# Sheet1.net
KiCad netlist of a schematic drawn in Altium Designer
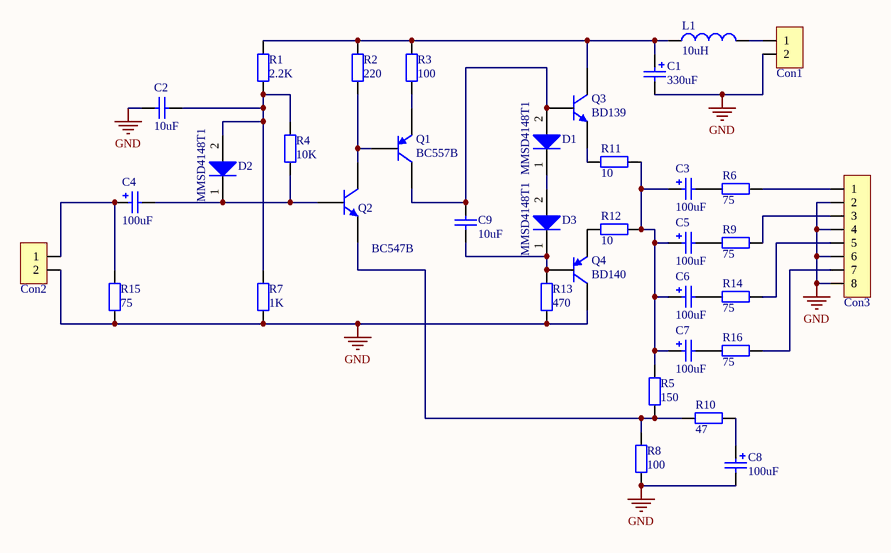
[diagram p0: Sheet1.SchDoc]

(export (version "E")
  (design (tool "Eeschema 10.0.6"))
  (components
    (comp (ref "C1")
      (value "330uF")
      (footprint "CAP Elect 8X4")
      (description "Polarized Capacitor (Radial)")
      (fields (field (name "Comment") "Cap Pol1"))
      (libsource (lib "miscellaneous") (part "Cap Pol1"))
    )
    (comp (ref "C2")
      (value "10uF")
      (footprint "H0805")
      (description "Capacitor")
      (fields (field (name "Comment") "Cap"))
      (libsource (lib "miscellaneous") (part "Cap"))
    )
    (comp (ref "C3")
      (value "100uF")
      (footprint "CAP Elect 5X2.5")
      (description "Polarized Capacitor (Radial)")
      (fields (field (name "Comment") "Cap Pol1"))
      (libsource (lib "miscellaneous") (part "Cap Pol1"))
    )
    (comp (ref "C4")
      (value "100uF")
      (footprint "CAP Elect 5X2.5")
      (description "Polarized Capacitor (Radial)")
      (fields (field (name "Comment") "Cap Pol1"))
      (libsource (lib "miscellaneous") (part "Cap Pol1"))
    )
    (comp (ref "C5")
      (value "100uF")
      (footprint "CAP Elect 5X2.5")
      (description "Polarized Capacitor (Radial)")
      (fields (field (name "Comment") "Cap Pol1"))
      (libsource (lib "miscellaneous") (part "Cap Pol1"))
    )
    (comp (ref "C6")
      (value "100uF")
      (footprint "CAP Elect 5X2.5")
      (description "Polarized Capacitor (Radial)")
      (fields (field (name "Comment") "Cap Pol1"))
      (libsource (lib "miscellaneous") (part "Cap Pol1"))
    )
    (comp (ref "C7")
      (value "100uF")
      (footprint "CAP Elect 5X2.5")
      (description "Polarized Capacitor (Radial)")
      (fields (field (name "Comment") "Cap Pol1"))
      (libsource (lib "miscellaneous") (part "Cap Pol1"))
    )
    (comp (ref "C8")
      (value "100uF")
      (footprint "CAP Elect 5X2.5")
      (description "Polarized Capacitor (Radial)")
      (fields (field (name "Comment") "Cap Pol1"))
      (libsource (lib "miscellaneous") (part "Cap Pol1"))
    )
    (comp (ref "C9")
      (value "10uF")
      (footprint "H0805")
      (description "Capacitor")
      (fields (field (name "Comment") "Cap"))
      (libsource (lib "miscellaneous") (part "Cap"))
    )
    (comp (ref "Con1")
      (value "XH-2A")
      (footprint "XH-2A")
      (description "2.5mm")
      (libsource (lib "Connector") (part "XH-2A"))
    )
    (comp (ref "Con2")
      (value "XH-2A")
      (footprint "XH-2A")
      (description "2.5mm")
      (libsource (lib "") (part "XH-2A_1"))
    )
    (comp (ref "Con3")
      (value "XH-8A")
      (footprint "XH-8A")
      (description "2.5mm")
      (libsource (lib "Connector") (part "XH-8A"))
    )
    (comp (ref "D1")
      (value "MMSD4148T1")
      (footprint "ONSC-SOD-123-2-425-04_V")
      (description "Switching Diode, 2-Pin SOD-123, Tape and Reel")
      (fields (field (name "MANUFACTURER") "On Semiconductor"))
      (libsource (lib "ON Semi Small Signal Switching Diodes") (part "MMSD4148T1"))
    )
    (comp (ref "D2")
      (value "MMSD4148T1")
      (footprint "ONSC-SOD-123-2-425-04_V")
      (description "Switching Diode, 2-Pin SOD-123, Tape and Reel")
      (fields (field (name "MANUFACTURER") "On Semiconductor"))
      (libsource (lib "ON Semi Small Signal Switching Diodes") (part "MMSD4148T1"))
    )
    (comp (ref "D3")
      (value "MMSD4148T1")
      (footprint "ONSC-SOD-123-2-425-04_V")
      (description "Switching Diode, 2-Pin SOD-123, Tape and Reel")
      (fields (field (name "MANUFACTURER") "On Semiconductor"))
      (libsource (lib "ON Semi Small Signal Switching Diodes") (part "MMSD4148T1"))
    )
    (comp (ref "L1")
      (value "10uH")
      (footprint "INDP7870X53N")
      (description "Inductor")
      (fields (field (name "PUBLISHER") "Altium Limited"))
      (libsource (lib "miscellaneous") (part "Inductor"))
    )
    (comp (ref "Q1")
      (value "BC557B")
      (footprint "SOT54")
      (description "PNP General-purpose Transistor")
      (fields (field (name "PUBLISHER") "Altium Limited"))
      (libsource (lib "Philips Discrete BJT - Low Power") (part "BC557B"))
    )
    (comp (ref "Q2")
      (value "BC547B")
      (footprint "SOT54")
      (description "NPN General-purpose Transistor")
      (fields (field (name "PUBLISHER") "Altium Limited"))
      (libsource (lib "Philips Discrete BJT - Low Power") (part "BC547B"))
    )
    (comp (ref "Q3")
      (value "BD139")
      (footprint "TO-126")
      (description "NPN SILICON TRANSISTORS")
      (libsource (lib "miscellaneous") (part "BD139"))
    )
    (comp (ref "Q4")
      (value "BD140")
      (footprint "TO-126")
      (description "PNP SILICON TRANSISTORS")
      (libsource (lib "miscellaneous") (part "BD140"))
    )
    (comp (ref "R1")
      (value "2.2K")
      (footprint "H0805")
      (description "Resistor")
      (fields (field (name "Comment") "Res2") (field (name "PUBLISHER") "Altium Limited"))
      (libsource (lib "") (part "Res2_1"))
    )
    (comp (ref "R2")
      (value "220")
      (footprint "H0805")
      (description "Resistor")
      (fields (field (name "Comment") "Res2") (field (name "PUBLISHER") "Altium Limited"))
      (libsource (lib "") (part "Res2_1"))
    )
    (comp (ref "R3")
      (value "100")
      (footprint "H0805")
      (description "Resistor")
      (fields (field (name "Comment") "Res2") (field (name "PUBLISHER") "Altium Limited"))
      (libsource (lib "") (part "Res2_1"))
    )
    (comp (ref "R4")
      (value "10K")
      (footprint "H0805")
      (description "Resistor")
      (fields (field (name "Comment") "Res2") (field (name "PUBLISHER") "Altium Limited"))
      (libsource (lib "") (part "Res2_1"))
    )
    (comp (ref "R5")
      (value "150")
      (footprint "H0805")
      (description "Resistor")
      (fields (field (name "Comment") "Res2") (field (name "PUBLISHER") "Altium Limited"))
      (libsource (lib "") (part "Res2_1"))
    )
    (comp (ref "R6")
      (value "75")
      (footprint "H0805")
      (description "Resistor")
      (fields (field (name "Comment") "Res2") (field (name "PUBLISHER") "Altium Limited"))
      (libsource (lib "Miscellaneous Devices") (part "Res2"))
    )
    (comp (ref "R7")
      (value "1K")
      (footprint "H0805")
      (description "Resistor")
      (fields (field (name "Comment") "Res2") (field (name "PUBLISHER") "Altium Limited"))
      (libsource (lib "") (part "Res2_1"))
    )
    (comp (ref "R8")
      (value "100")
      (footprint "H0805")
      (description "Resistor")
      (fields (field (name "Comment") "Res2") (field (name "PUBLISHER") "Altium Limited"))
      (libsource (lib "") (part "Res2_1"))
    )
    (comp (ref "R9")
      (value "75")
      (footprint "H0805")
      (description "Resistor")
      (fields (field (name "Comment") "Res2") (field (name "PUBLISHER") "Altium Limited"))
      (libsource (lib "Miscellaneous Devices") (part "Res2"))
    )
    (comp (ref "R10")
      (value "47")
      (footprint "H0805")
      (description "Resistor")
      (fields (field (name "Comment") "Res2") (field (name "PUBLISHER") "Altium Limited"))
      (libsource (lib "Miscellaneous Devices") (part "Res2"))
    )
    (comp (ref "R11")
      (value "10")
      (footprint "H1206")
      (description "Resistor")
      (fields (field (name "Comment") "Res2") (field (name "PUBLISHER") "Altium Limited"))
      (libsource (lib "Miscellaneous Devices") (part "Res2"))
    )
    (comp (ref "R12")
      (value "10")
      (footprint "H1206")
      (description "Resistor")
      (fields (field (name "Comment") "Res2") (field (name "PUBLISHER") "Altium Limited"))
      (libsource (lib "Miscellaneous Devices") (part "Res2"))
    )
    (comp (ref "R13")
      (value "470")
      (footprint "H0805")
      (description "Resistor")
      (fields (field (name "Comment") "Res2") (field (name "PUBLISHER") "Altium Limited"))
      (libsource (lib "") (part "Res2_1"))
    )
    (comp (ref "R14")
      (value "75")
      (footprint "H0805")
      (description "Resistor")
      (fields (field (name "Comment") "Res2") (field (name "PUBLISHER") "Altium Limited"))
      (libsource (lib "Miscellaneous Devices") (part "Res2"))
    )
    (comp (ref "R15")
      (value "75")
      (footprint "H0805")
      (description "Resistor")
      (fields (field (name "Comment") "Res2") (field (name "PUBLISHER") "Altium Limited"))
      (libsource (lib "") (part "Res2_1"))
    )
    (comp (ref "R16")
      (value "75")
      (footprint "H0805")
      (description "Resistor")
      (fields (field (name "Comment") "Res2") (field (name "PUBLISHER") "Altium Limited"))
      (libsource (lib "Miscellaneous Devices") (part "Res2"))
    )
  )
  (nets
    (net (code "1") (name "GND") (class "Default")
      (node (ref "C1") (pin "2") (pinfunction "2_2") (pintype "passive"))
      (node (ref "C2") (pin "2") (pinfunction "2_2") (pintype "passive"))
      (node (ref "C8") (pin "2") (pinfunction "2_2") (pintype "passive"))
      (node (ref "Con1") (pin "2") (pinfunction "2_2") (pintype "passive"))
      (node (ref "Con2") (pin "2") (pinfunction "2_2") (pintype "passive"))
      (node (ref "Con3") (pin "2") (pinfunction "2_2") (pintype "passive"))
      (node (ref "Con3") (pin "4") (pinfunction "4_4") (pintype "passive"))
      (node (ref "Con3") (pin "6") (pinfunction "6_6") (pintype "passive"))
      (node (ref "Con3") (pin "8") (pinfunction "8_8") (pintype "passive"))
      (node (ref "Q4") (pin "2") (pinfunction "C_2") (pintype "passive"))
      (node (ref "R13") (pin "1") (pinfunction "1_1") (pintype "passive"))
      (node (ref "R15") (pin "1") (pinfunction "1_1") (pintype "passive"))
      (node (ref "R7") (pin "1") (pinfunction "1_1") (pintype "passive"))
      (node (ref "R8") (pin "1") (pinfunction "1_1") (pintype "passive"))
    )
    (net (code "2") (name "Net-(C3-Pad1)") (class "Default")
      (node (ref "C3") (pin "1") (pinfunction "1_1") (pintype "passive"))
      (node (ref "C5") (pin "1") (pinfunction "1_1") (pintype "passive"))
      (node (ref "C6") (pin "1") (pinfunction "1_1") (pintype "passive"))
      (node (ref "C7") (pin "1") (pinfunction "1_1") (pintype "passive"))
      (node (ref "R11") (pin "1") (pinfunction "1_1") (pintype "passive"))
      (node (ref "R12") (pin "1") (pinfunction "1_1") (pintype "passive"))
      (node (ref "R5") (pin "2") (pinfunction "2_2") (pintype "passive"))
    )
    (net (code "3") (name "Net-(C3-Pad2)") (class "Default")
      (node (ref "C3") (pin "2") (pinfunction "2_2") (pintype "passive"))
      (node (ref "R6") (pin "2") (pinfunction "2_2") (pintype "passive"))
    )
    (net (code "4") (name "Net-(C4-Pad1)") (class "Default")
      (node (ref "C4") (pin "1") (pinfunction "1_1") (pintype "passive"))
      (node (ref "Con2") (pin "1") (pinfunction "1_1") (pintype "passive"))
      (node (ref "R15") (pin "2") (pinfunction "2_2") (pintype "passive"))
    )
    (net (code "5") (name "Net-(C5-Pad2)") (class "Default")
      (node (ref "C5") (pin "2") (pinfunction "2_2") (pintype "passive"))
      (node (ref "R9") (pin "2") (pinfunction "2_2") (pintype "passive"))
    )
    (net (code "6") (name "Net-(C6-Pad2)") (class "Default")
      (node (ref "C6") (pin "2") (pinfunction "2_2") (pintype "passive"))
      (node (ref "R14") (pin "2") (pinfunction "2_2") (pintype "passive"))
    )
    (net (code "7") (name "Net-(C7-Pad2)") (class "Default")
      (node (ref "C7") (pin "2") (pinfunction "2_2") (pintype "passive"))
      (node (ref "R16") (pin "2") (pinfunction "2_2") (pintype "passive"))
    )
    (net (code "8") (name "Net-(C8-Pad1)") (class "Default")
      (node (ref "C8") (pin "1") (pinfunction "1_1") (pintype "passive"))
      (node (ref "R10") (pin "1") (pinfunction "1_1") (pintype "passive"))
    )
    (net (code "9") (name "Net-(Con1-Pad1)") (class "Default")
      (node (ref "Con1") (pin "1") (pinfunction "1_1") (pintype "passive"))
      (node (ref "L1") (pin "2") (pinfunction "2_2") (pintype "passive"))
    )
    (net (code "10") (name "Net-(Con3-Pad1)") (class "Default")
      (node (ref "Con3") (pin "1") (pinfunction "1_1") (pintype "passive"))
      (node (ref "R6") (pin "1") (pinfunction "1_1") (pintype "passive"))
    )
    (net (code "11") (name "Net-(Con3-Pad3)") (class "Default")
      (node (ref "Con3") (pin "3") (pinfunction "3_3") (pintype "passive"))
      (node (ref "R9") (pin "1") (pinfunction "1_1") (pintype "passive"))
    )
    (net (code "12") (name "Net-(Con3-Pad5)") (class "Default")
      (node (ref "Con3") (pin "5") (pinfunction "5_5") (pintype "passive"))
      (node (ref "R14") (pin "1") (pinfunction "1_1") (pintype "passive"))
    )
    (net (code "13") (name "Net-(Con3-Pad7)") (class "Default")
      (node (ref "Con3") (pin "7") (pinfunction "7_7") (pintype "passive"))
      (node (ref "R16") (pin "1") (pinfunction "1_1") (pintype "passive"))
    )
    (net (code "14") (name "Net-(D1-A)") (class "Default")
      (node (ref "C9") (pin "2") (pinfunction "2_2") (pintype "passive"))
      (node (ref "D1") (pin "2") (pinfunction "A_2") (pintype "passive"))
      (node (ref "Q1") (pin "3") (pinfunction "C_3") (pintype "passive"))
      (node (ref "Q3") (pin "3") (pinfunction "B_3") (pintype "passive"))
    )
    (net (code "15") (name "Net-(D1-K)") (class "Default")
      (node (ref "D1") (pin "1") (pinfunction "K_1") (pintype "passive"))
      (node (ref "D3") (pin "2") (pinfunction "A_2") (pintype "passive"))
    )
    (net (code "16") (name "Net-(D2-A)") (class "Default")
      (node (ref "C2") (pin "1") (pinfunction "1_1") (pintype "passive"))
      (node (ref "D2") (pin "2") (pinfunction "A_2") (pintype "passive"))
      (node (ref "R1") (pin "1") (pinfunction "1_1") (pintype "passive"))
      (node (ref "R4") (pin "2") (pinfunction "2_2") (pintype "passive"))
      (node (ref "R7") (pin "2") (pinfunction "2_2") (pintype "passive"))
    )
    (net (code "17") (name "Net-(D2-K)") (class "Default")
      (node (ref "C4") (pin "2") (pinfunction "2_2") (pintype "passive"))
      (node (ref "D2") (pin "1") (pinfunction "K_1") (pintype "passive"))
      (node (ref "Q2") (pin "2") (pinfunction "B_2") (pintype "passive"))
      (node (ref "R4") (pin "1") (pinfunction "1_1") (pintype "passive"))
    )
    (net (code "18") (name "Net-(D3-K)") (class "Default")
      (node (ref "C9") (pin "1") (pinfunction "1_1") (pintype "passive"))
      (node (ref "D3") (pin "1") (pinfunction "K_1") (pintype "passive"))
      (node (ref "Q4") (pin "3") (pinfunction "B_3") (pintype "passive"))
      (node (ref "R13") (pin "2") (pinfunction "2_2") (pintype "passive"))
    )
    (net (code "19") (name "Net-(Q1-B)") (class "Default")
      (node (ref "Q1") (pin "2") (pinfunction "B_2") (pintype "passive"))
      (node (ref "Q2") (pin "3") (pinfunction "C_3") (pintype "passive"))
      (node (ref "R2") (pin "1") (pinfunction "1_1") (pintype "passive"))
    )
    (net (code "20") (name "Net-(Q1-E)") (class "Default")
      (node (ref "Q1") (pin "1") (pinfunction "E_1") (pintype "passive"))
      (node (ref "R3") (pin "1") (pinfunction "1_1") (pintype "passive"))
    )
    (net (code "21") (name "Net-(Q2-E)") (class "Default")
      (node (ref "Q2") (pin "1") (pinfunction "E_1") (pintype "passive"))
      (node (ref "R10") (pin "2") (pinfunction "2_2") (pintype "passive"))
      (node (ref "R5") (pin "1") (pinfunction "1_1") (pintype "passive"))
      (node (ref "R8") (pin "2") (pinfunction "2_2") (pintype "passive"))
    )
    (net (code "22") (name "Net-(Q3-C)") (class "Default")
      (node (ref "C1") (pin "1") (pinfunction "1_1") (pintype "passive"))
      (node (ref "L1") (pin "1") (pinfunction "1_1") (pintype "passive"))
      (node (ref "Q3") (pin "2") (pinfunction "C_2") (pintype "passive"))
      (node (ref "R1") (pin "2") (pinfunction "2_2") (pintype "passive"))
      (node (ref "R2") (pin "2") (pinfunction "2_2") (pintype "passive"))
      (node (ref "R3") (pin "2") (pinfunction "2_2") (pintype "passive"))
    )
    (net (code "23") (name "Net-(Q3-E)") (class "Default")
      (node (ref "Q3") (pin "1") (pinfunction "E_1") (pintype "passive"))
      (node (ref "R11") (pin "2") (pinfunction "2_2") (pintype "passive"))
    )
    (net (code "24") (name "Net-(Q4-E)") (class "Default")
      (node (ref "Q4") (pin "1") (pinfunction "E_1") (pintype "passive"))
      (node (ref "R12") (pin "2") (pinfunction "2_2") (pintype "passive"))
    )
  )
)
